# 00_-_Main.net
KiCad netlist of a schematic drawn in Altium Designer
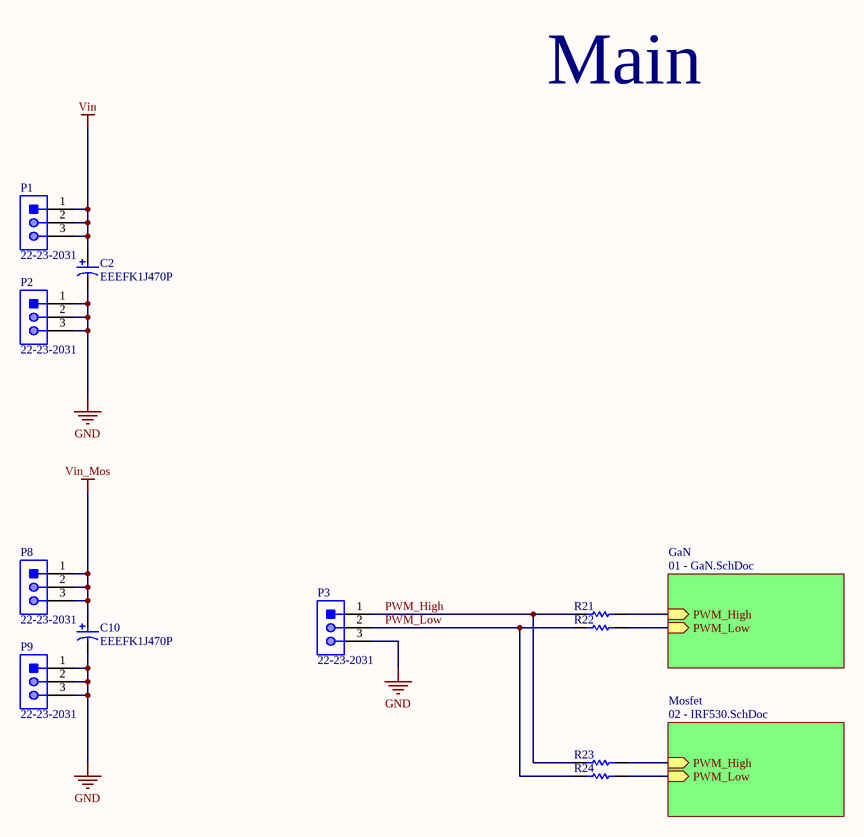
[diagram p0: 00 - Main.SchDoc]

(export (version "E")
  (design (tool "Eeschema 10.0.6"))
  (components
    (comp (ref "C2")
      (value "EEEFK1J470P")
      (footprint "PNSC-FK-V-F_V")
      (fields (field (name "MANUFACTURER") "Panasonic"))
      (libsource (lib "Altium Content Vault") (part "CAP-P-2"))
    )
    (comp (ref "C10")
      (value "EEEFK1J470P")
      (footprint "PNSC-FK-V-F_V")
      (fields (field (name "MANUFACTURER") "Panasonic"))
      (libsource (lib "Altium Content Vault") (part "CAP-P-2"))
    )
    (comp (ref "P1")
      (value "22-23-2031")
      (footprint "MOLX-22-23-2031_V")
      (description "Male Header, Pitch 2.54 mm, 1 x 3 Position, Height 8.18 mm, Tail Length 3.56 mm, RoHS, Bulk")
      (fields (field (name "MANUFACTURER") "Molex"))
      (libsource (lib "Altium Content Vault") (part "CN-1P-M-R3"))
    )
    (comp (ref "P2")
      (value "22-23-2031")
      (footprint "MOLX-22-23-2031_V")
      (description "Male Header, Pitch 2.54 mm, 1 x 3 Position, Height 8.18 mm, Tail Length 3.56 mm, RoHS, Bulk")
      (fields (field (name "MANUFACTURER") "Molex"))
      (libsource (lib "Altium Content Vault") (part "CN-1P-M-R3"))
    )
    (comp (ref "P3")
      (value "22-23-2031")
      (footprint "MOLX-22-23-2031_V")
      (description "Male Header, Pitch 2.54 mm, 1 x 3 Position, Height 8.18 mm, Tail Length 3.56 mm, RoHS, Bulk")
      (fields (field (name "MANUFACTURER") "Molex"))
      (libsource (lib "Altium Content Vault") (part "CN-1P-M-R3"))
    )
    (comp (ref "P8")
      (value "22-23-2031")
      (footprint "MOLX-22-23-2031_V")
      (description "Male Header, Pitch 2.54 mm, 1 x 3 Position, Height 8.18 mm, Tail Length 3.56 mm, RoHS, Bulk")
      (fields (field (name "MANUFACTURER") "Molex"))
      (libsource (lib "Altium Content Vault") (part "CN-1P-M-R3"))
    )
    (comp (ref "P9")
      (value "22-23-2031")
      (footprint "MOLX-22-23-2031_V")
      (description "Male Header, Pitch 2.54 mm, 1 x 3 Position, Height 8.18 mm, Tail Length 3.56 mm, RoHS, Bulk")
      (fields (field (name "MANUFACTURER") "Molex"))
      (libsource (lib "Altium Content Vault") (part "CN-1P-M-R3"))
    )
    (comp (ref "R21")
      (value "CRCW02010000Z0ED")
      (footprint "RESC0603X28X15NL5T05")
      (description "Chip Resistor, 0 Ohm, Jumper, 0.05 W, -55 to 155 degC, 0201 (0603 Metric), RoHS, Tape and Reel")
      (fields (field (name "TOLERANCE") "5%"))
      (libsource (lib "Altium Content Vault") (part "RES-2"))
    )
    (comp (ref "R22")
      (value "CRCW02010000Z0ED")
      (footprint "RESC0603X28X15NL5T05")
      (description "Chip Resistor, 0 Ohm, Jumper, 0.05 W, -55 to 155 degC, 0201 (0603 Metric), RoHS, Tape and Reel")
      (fields (field (name "TOLERANCE") "5%"))
      (libsource (lib "Altium Content Vault") (part "RES-2"))
    )
    (comp (ref "R23")
      (value "CRCW02010000Z0ED")
      (footprint "RESC0603X28X15NL5T05")
      (description "Chip Resistor, 0 Ohm, Jumper, 0.05 W, -55 to 155 degC, 0201 (0603 Metric), RoHS, Tape and Reel")
      (fields (field (name "TOLERANCE") "5%"))
      (libsource (lib "Altium Content Vault") (part "RES-2"))
    )
    (comp (ref "R24")
      (value "CRCW02010000Z0ED")
      (footprint "RESC0603X28X15NL5T05")
      (description "Chip Resistor, 0 Ohm, Jumper, 0.05 W, -55 to 155 degC, 0201 (0603 Metric), RoHS, Tape and Reel")
      (fields (field (name "TOLERANCE") "5%"))
      (libsource (lib "Altium Content Vault") (part "RES-2"))
    )
  )
  (nets
    (net (code "1") (name "/PWM_High") (class "Default")
      (node (ref "P3") (pin "1") (pinfunction "1_1") (pintype "passive"))
      (node (ref "R21") (pin "2") (pinfunction "2_2") (pintype "passive"))
      (node (ref "R23") (pin "2") (pinfunction "2_2") (pintype "passive"))
    )
    (net (code "2") (name "/PWM_High_1") (class "Default")
      (node (ref "R21") (pin "1") (pinfunction "1_1") (pintype "passive"))
    )
    (net (code "3") (name "/PWM_High_2") (class "Default")
      (node (ref "R23") (pin "1") (pinfunction "1_1") (pintype "passive"))
    )
    (net (code "4") (name "/PWM_Low") (class "Default")
      (node (ref "P3") (pin "2") (pinfunction "2_2") (pintype "passive"))
      (node (ref "R22") (pin "2") (pinfunction "2_2") (pintype "passive"))
      (node (ref "R24") (pin "2") (pinfunction "2_2") (pintype "passive"))
    )
    (net (code "5") (name "/PWM_Low_1") (class "Default")
      (node (ref "R22") (pin "1") (pinfunction "1_1") (pintype "passive"))
    )
    (net (code "6") (name "/PWM_Low_2") (class "Default")
      (node (ref "R24") (pin "1") (pinfunction "1_1") (pintype "passive"))
    )
    (net (code "7") (name "GND") (class "Default")
      (node (ref "C10") (pin "2") (pinfunction "2_2") (pintype "passive"))
      (node (ref "C2") (pin "2") (pinfunction "2_2") (pintype "passive"))
      (node (ref "P2") (pin "1") (pinfunction "1_1") (pintype "passive"))
      (node (ref "P2") (pin "2") (pinfunction "2_2") (pintype "passive"))
      (node (ref "P2") (pin "3") (pinfunction "3_3") (pintype "passive"))
      (node (ref "P3") (pin "3") (pinfunction "3_3") (pintype "passive"))
      (node (ref "P9") (pin "1") (pinfunction "1_1") (pintype "passive"))
      (node (ref "P9") (pin "2") (pinfunction "2_2") (pintype "passive"))
      (node (ref "P9") (pin "3") (pinfunction "3_3") (pintype "passive"))
    )
    (net (code "8") (name "Vin") (class "Default")
      (node (ref "C2") (pin "1") (pinfunction "1_1") (pintype "passive"))
      (node (ref "P1") (pin "1") (pinfunction "1_1") (pintype "passive"))
      (node (ref "P1") (pin "2") (pinfunction "2_2") (pintype "passive"))
      (node (ref "P1") (pin "3") (pinfunction "3_3") (pintype "passive"))
    )
    (net (code "9") (name "Vin_Mos") (class "Default")
      (node (ref "C10") (pin "1") (pinfunction "1_1") (pintype "passive"))
      (node (ref "P8") (pin "1") (pinfunction "1_1") (pintype "passive"))
      (node (ref "P8") (pin "2") (pinfunction "2_2") (pintype "passive"))
      (node (ref "P8") (pin "3") (pinfunction "3_3") (pintype "passive"))
    )
  )
)
